# schematicembedded.net
KiCad netlist of a schematic drawn in Altium Designer
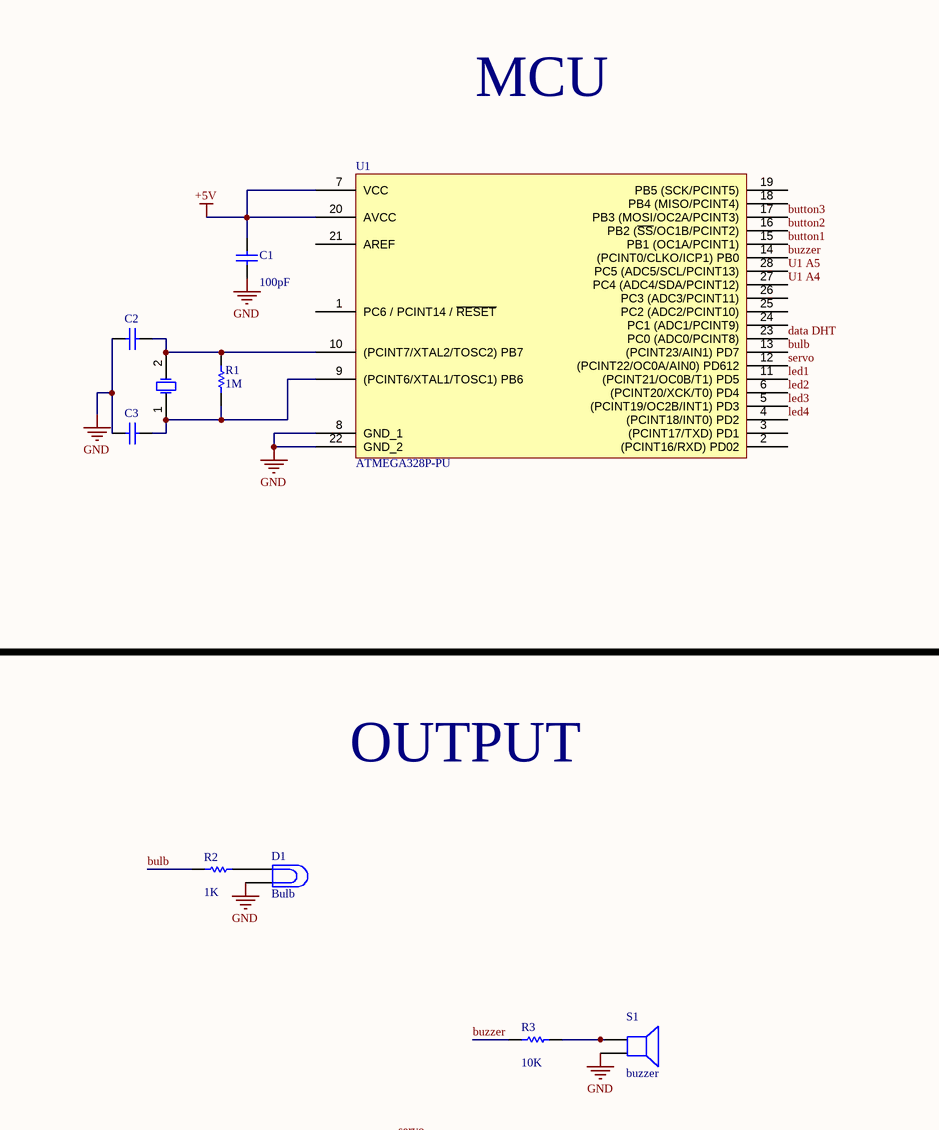
[diagram p0: schematicembedded.SchDoc, top left]
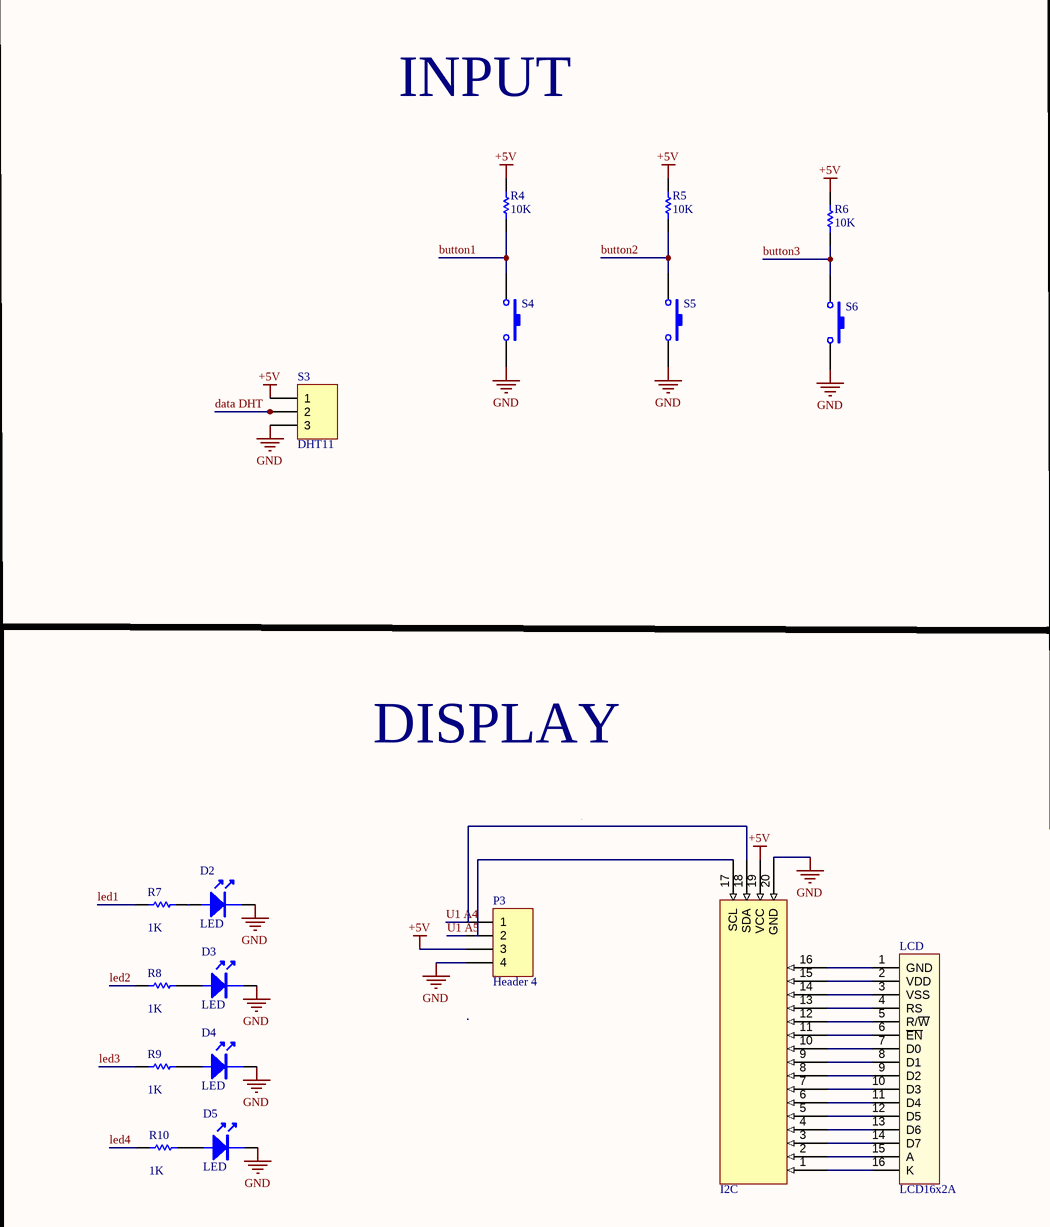
[diagram p1: schematicembedded.SchDoc, top right]
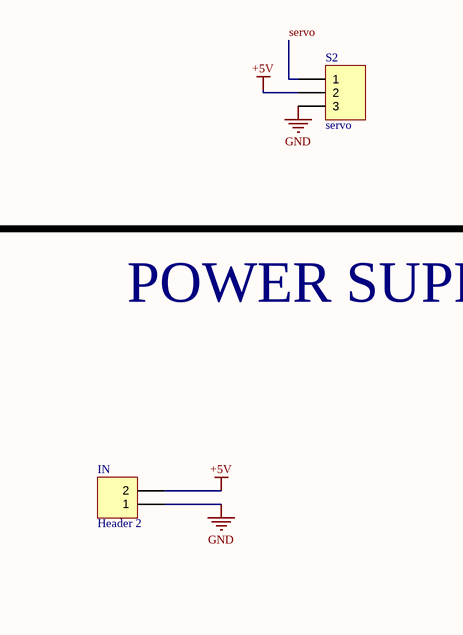
[diagram p2: schematicembedded.SchDoc, bottom left]

(export (version "E")
  (design (tool "Eeschema 10.0.6"))
  (components
    (comp (ref "C1")
      (value "100pF")
      (footprint "RAD-0.3")
      (description "Capacitor")
      (fields (field (name "Comment") "Cap") (field (name "PUBLISHER") "Altium Limited"))
      (libsource (lib "Miscellaneous Devices") (part "Cap"))
    )
    (comp (ref "C2")
      (value "Cap")
      (footprint "RAD-0.3")
      (description "Capacitor")
      (fields (field (name "PUBLISHER") "Altium Limited"))
      (libsource (lib "Miscellaneous Devices") (part "Cap"))
    )
    (comp (ref "C3")
      (value "Cap")
      (footprint "RAD-0.3")
      (description "Capacitor")
      (fields (field (name "PUBLISHER") "Altium Limited"))
      (libsource (lib "Miscellaneous Devices") (part "Cap"))
    )
    (comp (ref "D1")
      (value "Bulb")
      (footprint "PIN2")
      (description "Incandescent Bulb")
      (fields (field (name "PUBLISHER") "Altium Limited"))
      (libsource (lib "Miscellaneous Devices") (part "Lamp"))
    )
    (comp (ref "D2") (value "LED") (footprint "CAP10UF") (libsource (lib "Cty1") (part "LED")))
    (comp (ref "D3") (value "LED") (footprint "CAP10UF") (libsource (lib "Cty1") (part "LED")))
    (comp (ref "D4") (value "LED") (footprint "CAP10UF") (libsource (lib "Cty1") (part "LED")))
    (comp (ref "D5") (value "LED") (footprint "CAP10UF") (libsource (lib "Cty1") (part "LED")))
    (comp (ref "I2C") (value "Component_1") (libsource (lib "I2C") (part "Component_1")))
    (comp (ref "IN")
      (value "Header 2")
      (footprint "HDR1X2")
      (description "Header, 2-Pin")
      (fields (field (name "PUBLISHER") "Altium Limited"))
      (libsource (lib "Miscellaneous Connectors") (part "Header 2"))
    )
    (comp (ref "LCD")
      (value "LCD16x2A")
      (footprint "LCD16X2")
      (description "LCD dipslay 16 char, 2 line")
      (libsource (lib "VioletofSun") (part "LCD16x2"))
    )
    (comp (ref "P3")
      (value "Header 4")
      (footprint "HDR1X4")
      (description "Header, 4-Pin")
      (fields (field (name "PUBLISHER") "Altium Limited"))
      (libsource (lib "Miscellaneous Connectors") (part "Header 4"))
    )
    (comp (ref "R1")
      (value "1M")
      (footprint "AXIAL-0.3")
      (description "Resistor")
      (fields (field (name "Comment") "Res1") (field (name "PUBLISHER") "Altium Limited"))
      (libsource (lib "Miscellaneous Devices") (part "Res1"))
    )
    (comp (ref "R2")
      (value "1K")
      (footprint "AXIAL-0.3")
      (description "Resistor")
      (fields (field (name "Comment") "Res1") (field (name "PUBLISHER") "Altium Limited"))
      (libsource (lib "Miscellaneous Devices") (part "Res1"))
    )
    (comp (ref "R3")
      (value "10K")
      (footprint "AXIAL-0.3")
      (description "Resistor")
      (fields (field (name "Comment") "Res1") (field (name "PUBLISHER") "Altium Limited"))
      (libsource (lib "Miscellaneous Devices") (part "Res1"))
    )
    (comp (ref "R4")
      (value "10K")
      (footprint "AXIAL-0.3")
      (description "Resistor")
      (fields (field (name "Comment") "Res1") (field (name "PUBLISHER") "Altium Limited"))
      (libsource (lib "Miscellaneous Devices") (part "Res1"))
    )
    (comp (ref "R5")
      (value "10K")
      (footprint "AXIAL-0.3")
      (description "Resistor")
      (fields (field (name "Comment") "Res1") (field (name "PUBLISHER") "Altium Limited"))
      (libsource (lib "Miscellaneous Devices") (part "Res1"))
    )
    (comp (ref "R6")
      (value "10K")
      (footprint "AXIAL-0.3")
      (description "Resistor")
      (fields (field (name "Comment") "Res1") (field (name "PUBLISHER") "Altium Limited"))
      (libsource (lib "Miscellaneous Devices") (part "Res1"))
    )
    (comp (ref "R7")
      (value "1K")
      (footprint "AXIAL-0.3")
      (description "Resistor")
      (fields (field (name "Comment") "Res1") (field (name "PUBLISHER") "Altium Limited"))
      (libsource (lib "Miscellaneous Devices") (part "Res1"))
    )
    (comp (ref "R8")
      (value "1K")
      (footprint "AXIAL-0.3")
      (description "Resistor")
      (fields (field (name "Comment") "Res1") (field (name "PUBLISHER") "Altium Limited"))
      (libsource (lib "Miscellaneous Devices") (part "Res1"))
    )
    (comp (ref "R9")
      (value "1K")
      (footprint "AXIAL-0.3")
      (description "Resistor")
      (fields (field (name "Comment") "Res1") (field (name "PUBLISHER") "Altium Limited"))
      (libsource (lib "Miscellaneous Devices") (part "Res1"))
    )
    (comp (ref "R10")
      (value "1K")
      (footprint "AXIAL-0.3")
      (description "Resistor")
      (fields (field (name "Comment") "Res1") (field (name "PUBLISHER") "Altium Limited"))
      (libsource (lib "Miscellaneous Devices") (part "Res1"))
    )
    (comp (ref "S1")
      (value "buzzer")
      (footprint "PIN2")
      (description "Loudspeaker")
      (fields (field (name "PUBLISHER") "Altium Limited"))
      (libsource (lib "Miscellaneous Devices") (part "Speaker"))
    )
    (comp (ref "S2")
      (value "servo")
      (footprint "HDR1X3")
      (description "Header, 3-Pin")
      (fields (field (name "PUBLISHER") "Altium Limited"))
      (libsource (lib "Miscellaneous Connectors") (part "Header 3"))
    )
    (comp (ref "S3")
      (value "DHT11")
      (footprint "HDR1X3")
      (description "Header, 3-Pin")
      (fields (field (name "PUBLISHER") "Altium Limited"))
      (libsource (lib "Miscellaneous Connectors") (part "Header 3"))
    )
    (comp (ref "S4")
      (value "SW-PB")
      (footprint "SPST-2")
      (description "Switch")
      (fields (field (name "PUBLISHER") "Altium Limited"))
      (libsource (lib "Miscellaneous Devices") (part "SW-PB"))
    )
    (comp (ref "S5")
      (value "SW-PB")
      (footprint "SPST-2")
      (description "Switch")
      (fields (field (name "PUBLISHER") "Altium Limited"))
      (libsource (lib "Miscellaneous Devices") (part "SW-PB"))
    )
    (comp (ref "S6")
      (value "SW-PB")
      (footprint "SPST-2")
      (description "Switch")
      (fields (field (name "PUBLISHER") "Altium Limited"))
      (libsource (lib "Miscellaneous Devices") (part "SW-PB"))
    )
    (comp (ref "U1")
      (value "ATMEGA328P-PU")
      (footprint "27_DIP_7.62mm")
      (description "ATMEGA328P-PU; 8 bit Microcontroller AVR 20MHz 1; 32kb Flash; 2kb RAM; I2C SPI 2")
      (fields (field (name "MANUFACTURER") "Microchip / Atmel"))
      (libsource (lib "ATMEGA328P-PU") (part "ATMEGA328P-PU"))
    )
    (comp (ref "Y1")
      (value "XTAL")
      (footprint "R38")
      (description "Crystal Oscillator")
      (fields (field (name "PUBLISHER") "Altium Limited"))
      (libsource (lib "Miscellaneous Devices") (part "XTAL"))
    )
  )
  (nets
    (net (code "1") (name "+5V") (class "Default")
      (node (ref "C1") (pin "2") (pinfunction "2_2") (pintype "passive"))
      (node (ref "I2C") (pin "19") (pinfunction "VCC_19") (pintype "input"))
      (node (ref "IN") (pin "2") (pinfunction "2_2") (pintype "passive"))
      (node (ref "P3") (pin "3") (pinfunction "3_3") (pintype "passive"))
      (node (ref "R4") (pin "2") (pinfunction "2_2") (pintype "passive"))
      (node (ref "R5") (pin "2") (pinfunction "2_2") (pintype "passive"))
      (node (ref "R6") (pin "2") (pinfunction "2_2") (pintype "passive"))
      (node (ref "S2") (pin "2") (pinfunction "2_2") (pintype "passive"))
      (node (ref "S3") (pin "1") (pinfunction "1_1") (pintype "passive"))
      (node (ref "U1") (pin "20") (pinfunction "AVCC_20") (pintype "passive"))
      (node (ref "U1") (pin "7") (pinfunction "VCC_7") (pintype "passive"))
    )
    (net (code "2") (name "/U1 A4") (class "Default")
      (node (ref "P3") (pin "1") (pinfunction "1_1") (pintype "passive"))
      (node (ref "U1") (pin "27") (pinfunction "PC4_(ADC4/SDA/PCINT12)_27") (pintype "passive"))
    )
    (net (code "3") (name "/U1 A5") (class "Default")
      (node (ref "P3") (pin "2") (pinfunction "2_2") (pintype "passive"))
      (node (ref "U1") (pin "28") (pinfunction "PC5_(ADC5/SCL/PCINT13)_28") (pintype "passive"))
    )
    (net (code "4") (name "/bulb") (class "Default")
      (node (ref "R2") (pin "1") (pinfunction "1_1") (pintype "passive"))
      (node (ref "U1") (pin "13") (pinfunction "(PCINT23/AIN1)_PD7_13") (pintype "passive"))
    )
    (net (code "5") (name "/button1") (class "Default")
      (node (ref "R4") (pin "1") (pinfunction "1_1") (pintype "passive"))
      (node (ref "S4") (pin "1") (pinfunction "1_1") (pintype "passive"))
      (node (ref "U1") (pin "15") (pinfunction "PB1_(OC1A/PCINT1)_15") (pintype "passive"))
    )
    (net (code "6") (name "/button2") (class "Default")
      (node (ref "R5") (pin "1") (pinfunction "1_1") (pintype "passive"))
      (node (ref "S5") (pin "1") (pinfunction "1_1") (pintype "passive"))
      (node (ref "U1") (pin "16") (pinfunction "PB2_(~{SS}/OC1B/PCINT2)_16") (pintype "passive"))
    )
    (net (code "7") (name "/button3") (class "Default")
      (node (ref "R6") (pin "1") (pinfunction "1_1") (pintype "passive"))
      (node (ref "S6") (pin "1") (pinfunction "1_1") (pintype "passive"))
      (node (ref "U1") (pin "17") (pinfunction "PB3_(MOSI/OC2A/PCINT3)_17") (pintype "passive"))
    )
    (net (code "8") (name "/buzzer") (class "Default")
      (node (ref "R3") (pin "1") (pinfunction "1_1") (pintype "passive"))
      (node (ref "U1") (pin "14") (pinfunction "(PCINT0/CLKO/ICP1)_PB0_14") (pintype "passive"))
    )
    (net (code "9") (name "/data DHT") (class "Default")
      (node (ref "S3") (pin "2") (pinfunction "2_2") (pintype "passive"))
      (node (ref "U1") (pin "23") (pinfunction "PC0_(ADC0/PCINT8)_23") (pintype "passive"))
    )
    (net (code "10") (name "/led1") (class "Default")
      (node (ref "R7") (pin "1") (pinfunction "1_1") (pintype "passive"))
      (node (ref "U1") (pin "11") (pinfunction "(PCINT21/OC0B/T1)_PD5_11") (pintype "passive"))
    )
    (net (code "11") (name "/led2") (class "Default")
      (node (ref "R8") (pin "1") (pinfunction "1_1") (pintype "passive"))
      (node (ref "U1") (pin "6") (pinfunction "(PCINT20/XCK/T0)_PD4_6") (pintype "passive"))
    )
    (net (code "12") (name "/led3") (class "Default")
      (node (ref "R9") (pin "1") (pinfunction "1_1") (pintype "passive"))
      (node (ref "U1") (pin "5") (pinfunction "(PCINT19/OC2B/INT1)_PD3_5") (pintype "passive"))
    )
    (net (code "13") (name "/led4") (class "Default")
      (node (ref "R10") (pin "1") (pinfunction "1_1") (pintype "passive"))
      (node (ref "U1") (pin "4") (pinfunction "(PCINT18/INT0)_PD2_4") (pintype "passive"))
    )
    (net (code "14") (name "/servo") (class "Default")
      (node (ref "S2") (pin "1") (pinfunction "1_1") (pintype "passive"))
      (node (ref "U1") (pin "12") (pinfunction "(PCINT22/OC0A/AIN0)_PD612_12") (pintype "passive"))
    )
    (net (code "15") (name "GND") (class "Default")
      (node (ref "C1") (pin "1") (pinfunction "1_1") (pintype "passive"))
      (node (ref "C2") (pin "2") (pinfunction "2_2") (pintype "passive"))
      (node (ref "C3") (pin "2") (pinfunction "2_2") (pintype "passive"))
      (node (ref "D1") (pin "2") (pinfunction "2_2") (pintype "passive"))
      (node (ref "D2") (pin "2") (pinfunction "2_2") (pintype "passive"))
      (node (ref "D3") (pin "2") (pinfunction "2_2") (pintype "passive"))
      (node (ref "D4") (pin "2") (pinfunction "2_2") (pintype "passive"))
      (node (ref "D5") (pin "2") (pinfunction "2_2") (pintype "passive"))
      (node (ref "I2C") (pin "20") (pinfunction "GND_20") (pintype "input"))
      (node (ref "IN") (pin "1") (pinfunction "1_1") (pintype "passive"))
      (node (ref "P3") (pin "4") (pinfunction "4_4") (pintype "passive"))
      (node (ref "S1") (pin "2") (pinfunction "2_2") (pintype "passive"))
      (node (ref "S2") (pin "3") (pinfunction "3_3") (pintype "passive"))
      (node (ref "S3") (pin "3") (pinfunction "3_3") (pintype "passive"))
      (node (ref "S4") (pin "2") (pinfunction "2_2") (pintype "passive"))
      (node (ref "S5") (pin "2") (pinfunction "2_2") (pintype "passive"))
      (node (ref "S6") (pin "2") (pinfunction "2_2") (pintype "passive"))
      (node (ref "U1") (pin "22") (pinfunction "GND_2_22") (pintype "passive"))
      (node (ref "U1") (pin "8") (pinfunction "GND_1_8") (pintype "passive"))
    )
    (net (code "16") (name "Net-(D1-Pad1)") (class "Default")
      (node (ref "D1") (pin "1") (pinfunction "1_1") (pintype "passive"))
      (node (ref "R2") (pin "2") (pinfunction "2_2") (pintype "passive"))
    )
    (net (code "17") (name "Net-(D2-Pad1)") (class "Default")
      (node (ref "D2") (pin "1") (pinfunction "1_1") (pintype "passive"))
      (node (ref "R7") (pin "2") (pinfunction "2_2") (pintype "passive"))
    )
    (net (code "18") (name "Net-(D3-Pad1)") (class "Default")
      (node (ref "D3") (pin "1") (pinfunction "1_1") (pintype "passive"))
      (node (ref "R8") (pin "2") (pinfunction "2_2") (pintype "passive"))
    )
    (net (code "19") (name "Net-(D4-Pad1)") (class "Default")
      (node (ref "D4") (pin "1") (pinfunction "1_1") (pintype "passive"))
      (node (ref "R9") (pin "2") (pinfunction "2_2") (pintype "passive"))
    )
    (net (code "20") (name "Net-(D5-Pad1)") (class "Default")
      (node (ref "D5") (pin "1") (pinfunction "1_1") (pintype "passive"))
      (node (ref "R10") (pin "2") (pinfunction "2_2") (pintype "passive"))
    )
    (net (code "21") (name "Net-(LCD-A)") (class "Default")
      (node (ref "I2C") (pin "2") (pintype "input"))
      (node (ref "LCD") (pin "15") (pinfunction "A_15") (pintype "passive"))
    )
    (net (code "22") (name "Net-(LCD-D0)") (class "Default")
      (node (ref "I2C") (pin "10") (pintype "input"))
      (node (ref "LCD") (pin "7") (pinfunction "D0_7") (pintype "passive"))
    )
    (net (code "23") (name "Net-(LCD-D1)") (class "Default")
      (node (ref "I2C") (pin "9") (pintype "input"))
      (node (ref "LCD") (pin "8") (pinfunction "D1_8") (pintype "passive"))
    )
    (net (code "24") (name "Net-(LCD-D2)") (class "Default")
      (node (ref "I2C") (pin "8") (pintype "input"))
      (node (ref "LCD") (pin "9") (pinfunction "D2_9") (pintype "passive"))
    )
    (net (code "25") (name "Net-(LCD-D3)") (class "Default")
      (node (ref "I2C") (pin "7") (pintype "input"))
      (node (ref "LCD") (pin "10") (pinfunction "D3_10") (pintype "passive"))
    )
    (net (code "26") (name "Net-(LCD-D4)") (class "Default")
      (node (ref "I2C") (pin "6") (pintype "input"))
      (node (ref "LCD") (pin "11") (pinfunction "D4_11") (pintype "passive"))
    )
    (net (code "27") (name "Net-(LCD-D5)") (class "Default")
      (node (ref "I2C") (pin "5") (pintype "input"))
      (node (ref "LCD") (pin "12") (pinfunction "D5_12") (pintype "passive"))
    )
    (net (code "28") (name "Net-(LCD-D6)") (class "Default")
      (node (ref "I2C") (pin "4") (pintype "input"))
      (node (ref "LCD") (pin "13") (pinfunction "D6_13") (pintype "passive"))
    )
    (net (code "29") (name "Net-(LCD-D7)") (class "Default")
      (node (ref "I2C") (pin "3") (pintype "input"))
      (node (ref "LCD") (pin "14") (pinfunction "D7_14") (pintype "passive"))
    )
    (net (code "30") (name "Net-(LCD-GND)") (class "Default")
      (node (ref "I2C") (pin "16") (pintype "input"))
      (node (ref "LCD") (pin "1") (pinfunction "GND_1") (pintype "passive"))
    )
    (net (code "31") (name "Net-(LCD-K)") (class "Default")
      (node (ref "I2C") (pin "1") (pintype "input"))
      (node (ref "LCD") (pin "16") (pinfunction "K_16") (pintype "passive"))
    )
    (net (code "32") (name "Net-(LCD-RS)") (class "Default")
      (node (ref "I2C") (pin "13") (pintype "input"))
      (node (ref "LCD") (pin "4") (pinfunction "RS_4") (pintype "passive"))
    )
    (net (code "33") (name "Net-(LCD-R{slash}~{W})") (class "Default")
      (node (ref "I2C") (pin "12") (pintype "input"))
      (node (ref "LCD") (pin "5") (pinfunction "R/~{W}_5") (pintype "passive"))
    )
    (net (code "34") (name "Net-(LCD-VDD)") (class "Default")
      (node (ref "I2C") (pin "15") (pintype "input"))
      (node (ref "LCD") (pin "2") (pinfunction "VDD_2") (pintype "passive"))
    )
    (net (code "35") (name "Net-(LCD-VSS)") (class "Default")
      (node (ref "I2C") (pin "14") (pintype "input"))
      (node (ref "LCD") (pin "3") (pinfunction "VSS_3") (pintype "passive"))
    )
    (net (code "36") (name "Net-(LCD-~{EN})") (class "Default")
      (node (ref "I2C") (pin "11") (pintype "input"))
      (node (ref "LCD") (pin "6") (pinfunction "~{EN}_6") (pintype "passive"))
    )
    (net (code "37") (name "Net-(R3-Pad2)") (class "Default")
      (node (ref "R3") (pin "2") (pinfunction "2_2") (pintype "passive"))
      (node (ref "S1") (pin "1") (pinfunction "1_1") (pintype "passive"))
    )
    (net (code "38") (name "Net-(U1-(PCINT6{slash}XTAL1{slash}TOSC1)_PB6)") (class "Default")
      (node (ref "C3") (pin "1") (pinfunction "1_1") (pintype "passive"))
      (node (ref "R1") (pin "1") (pinfunction "1_1") (pintype "passive"))
      (node (ref "U1") (pin "9") (pinfunction "(PCINT6/XTAL1/TOSC1)_PB6_9") (pintype "passive"))
      (node (ref "Y1") (pin "1") (pinfunction "OSC1_1") (pintype "passive"))
    )
    (net (code "39") (name "Net-(U1-(PCINT7{slash}XTAL2{slash}TOSC2)_PB7)") (class "Default")
      (node (ref "C2") (pin "1") (pinfunction "1_1") (pintype "passive"))
      (node (ref "R1") (pin "2") (pinfunction "2_2") (pintype "passive"))
      (node (ref "U1") (pin "10") (pinfunction "(PCINT7/XTAL2/TOSC2)_PB7_10") (pintype "passive"))
      (node (ref "Y1") (pin "2") (pinfunction "OSC2_2") (pintype "passive"))
    )
    (net (code "40") (name "unconnected-(I2C-SCL-Pad17)") (class "Default")
      (node (ref "I2C") (pin "17") (pinfunction "SCL_17") (pintype "input"))
    )
    (net (code "41") (name "unconnected-(I2C-SDA-Pad18)") (class "Default")
      (node (ref "I2C") (pin "18") (pinfunction "SDA_18") (pintype "input"))
    )
    (net (code "42") (name "unconnected-(U1-(PCINT16{slash}RXD)_PD02-Pad2)") (class "Default")
      (node (ref "U1") (pin "2") (pinfunction "(PCINT16/RXD)_PD02_2") (pintype "passive"))
    )
    (net (code "43") (name "unconnected-(U1-(PCINT17{slash}TXD)_PD1-Pad3)") (class "Default")
      (node (ref "U1") (pin "3") (pinfunction "(PCINT17/TXD)_PD1_3") (pintype "passive"))
    )
    (net (code "44") (name "unconnected-(U1-AREF-Pad21)") (class "Default")
      (node (ref "U1") (pin "21") (pinfunction "AREF_21") (pintype "passive"))
    )
    (net (code "45") (name "unconnected-(U1-PB4_(MISO{slash}PCINT4)-Pad18)") (class "Default")
      (node (ref "U1") (pin "18") (pinfunction "PB4_(MISO/PCINT4)_18") (pintype "passive"))
    )
    (net (code "46") (name "unconnected-(U1-PB5_(SCK{slash}PCINT5)-Pad19)") (class "Default")
      (node (ref "U1") (pin "19") (pinfunction "PB5_(SCK/PCINT5)_19") (pintype "passive"))
    )
    (net (code "47") (name "unconnected-(U1-PC1_(ADC1{slash}PCINT9)-Pad24)") (class "Default")
      (node (ref "U1") (pin "24") (pinfunction "PC1_(ADC1/PCINT9)_24") (pintype "passive"))
    )
    (net (code "48") (name "unconnected-(U1-PC2_(ADC2{slash}PCINT10)-Pad25)") (class "Default")
      (node (ref "U1") (pin "25") (pinfunction "PC2_(ADC2/PCINT10)_25") (pintype "passive"))
    )
    (net (code "49") (name "unconnected-(U1-PC3_(ADC3{slash}PCINT11)-Pad26)") (class "Default")
      (node (ref "U1") (pin "26") (pinfunction "PC3_(ADC3/PCINT11)_26") (pintype "passive"))
    )
    (net (code "50") (name "unconnected-(U1-PC6_{slash}_PCINT14_{slash}_~{RESET}-Pad1)") (class "Default")
      (node (ref "U1") (pin "1") (pinfunction "PC6_/_PCINT14_/_~{RESET}_1") (pintype "passive"))
    )
  )
)
